# SCH_WETBCV1.net
KiCad netlist of a schematic drawn in Altium Designer
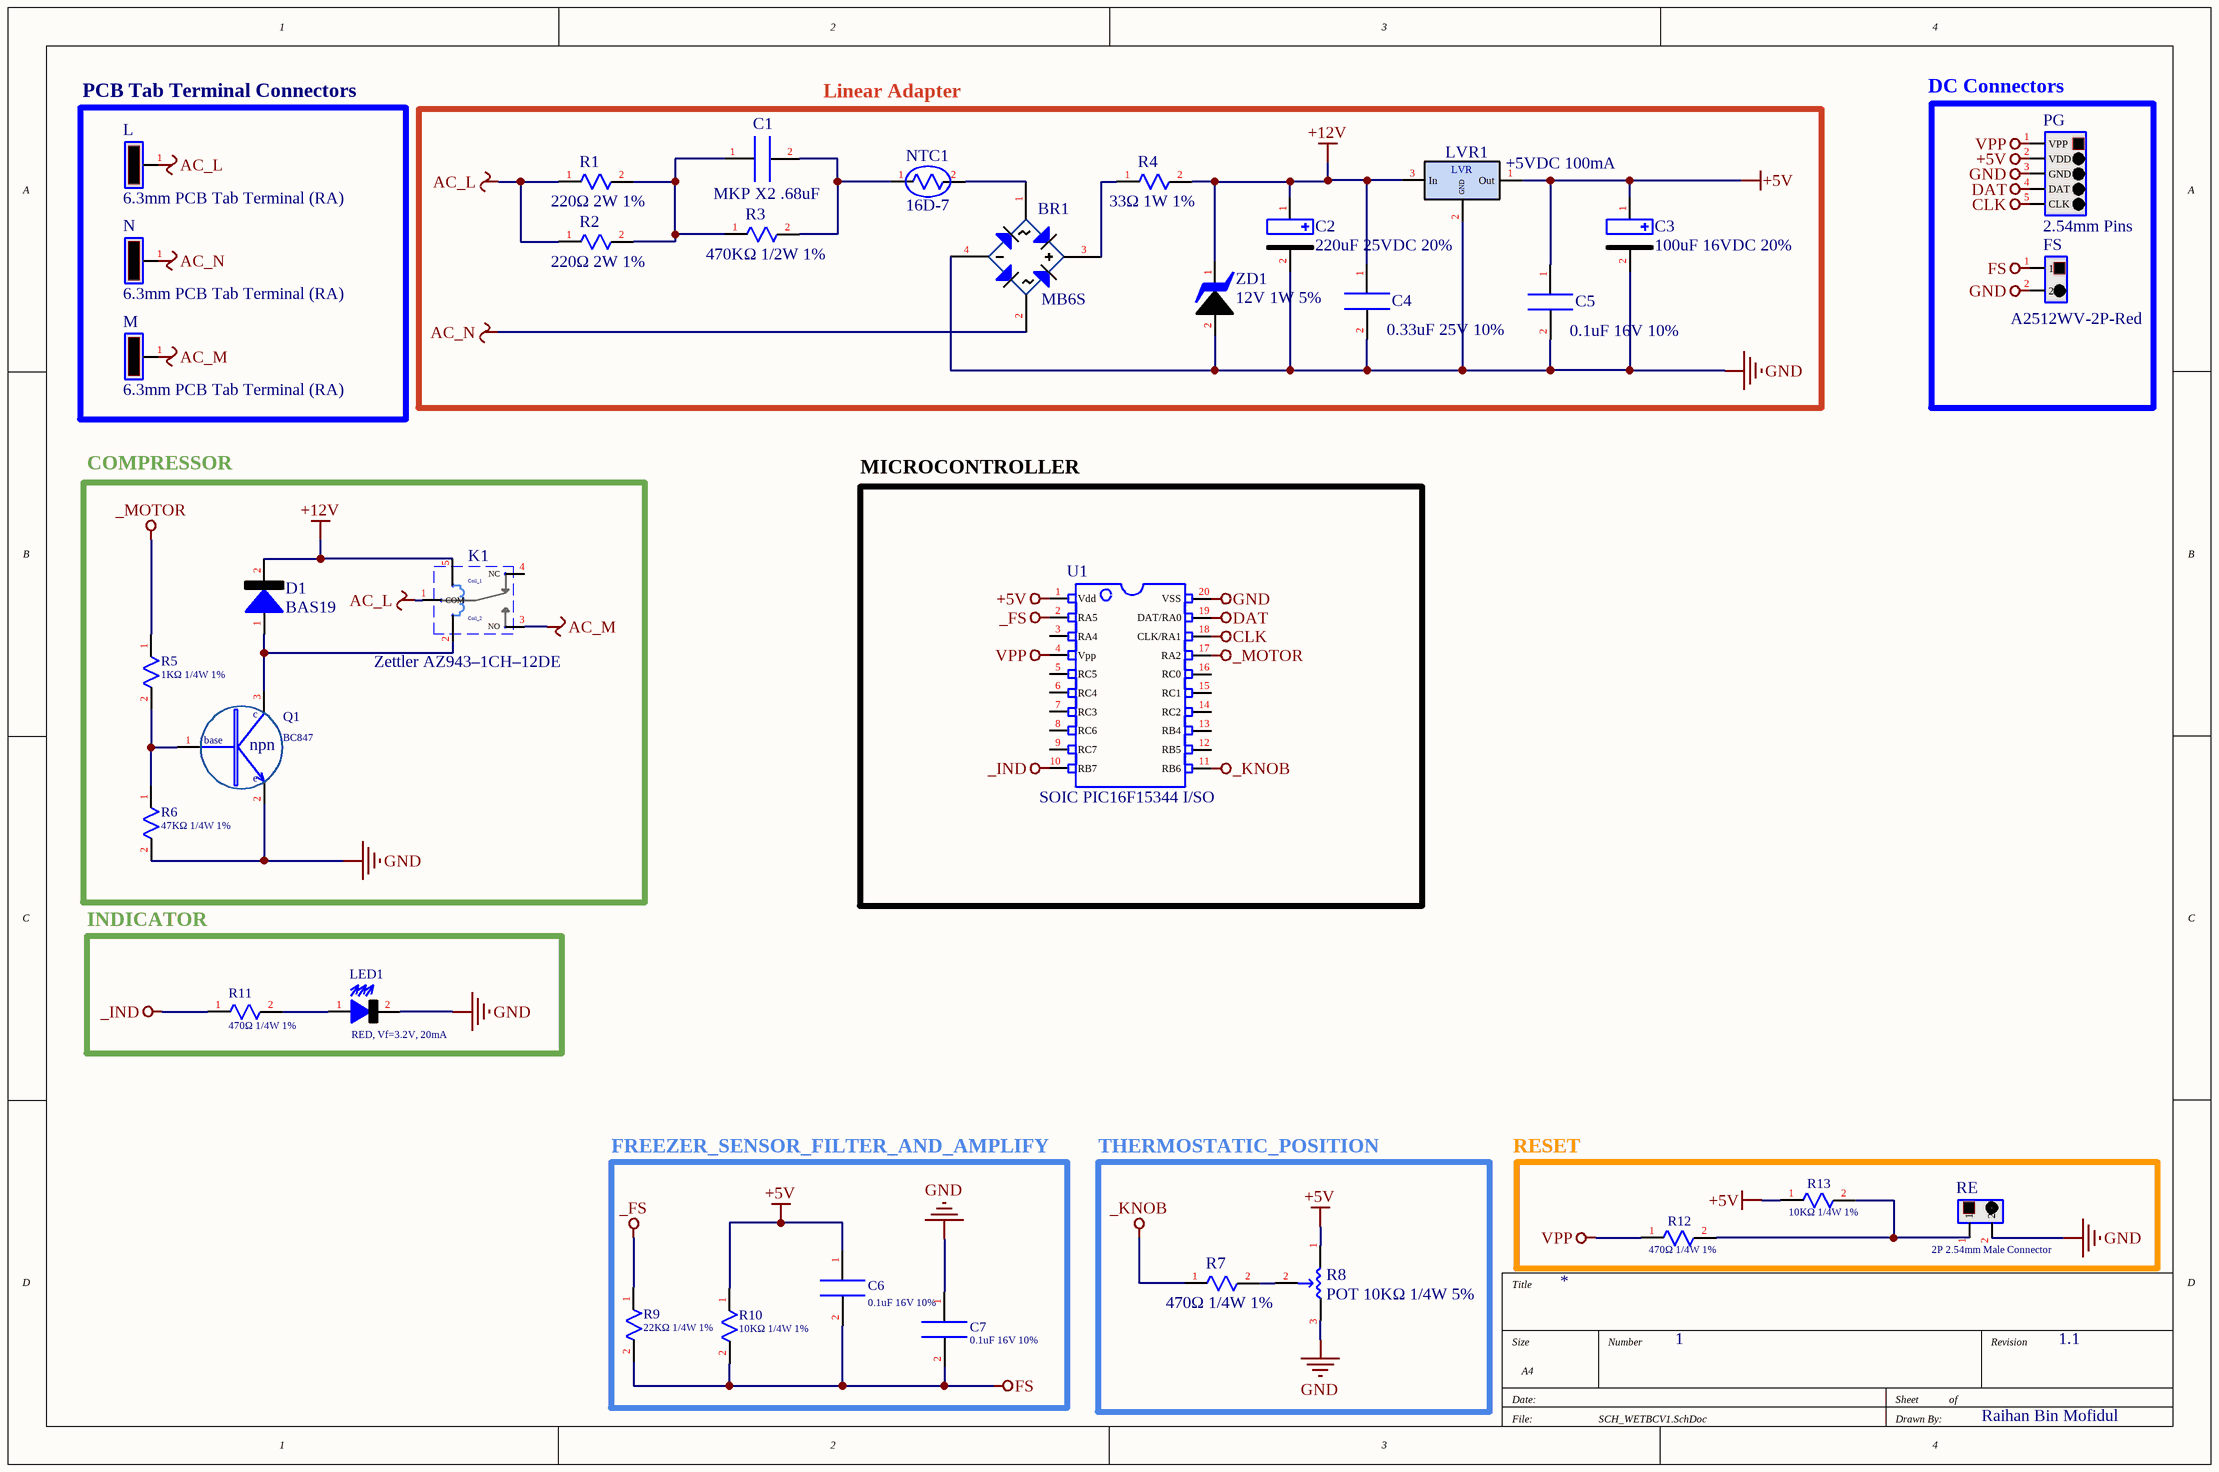
[diagram p0: SCH_WETBCV1.SchDoc]

(export (version "E")
  (design (tool "Eeschema 10.0.6"))
  (components
    (comp (ref "BR1")
      (value "MB6S")
      (footprint "BR_SMD_MB6S")
      (description "BRIDGE RECT 1P 600V 500MA 4SOIC, ON-SEMICONDUCTOR")
      (libsource (lib "RBM_SCH-LIB_02-SEP-19") (part "Bridge Rectifier"))
    )
    (comp (ref "C1")
      (value "MKP X2 .68uF")
      (footprint "C_X2_18X10X15.8_P15")
      (description "684K310V P=15 18*9.5*15.5 Climate-category: 40/110/56")
      (libsource (lib "RBM_SCH-LIB_02-SEP-19") (part "Capacitor Non-Polar"))
    )
    (comp (ref "C2")
      (value "220uF 25VDC 20%")
      (footprint "C_Radial_P3.5")
      (description "Ø8*11mm 3.5mm Pitch")
      (libsource (lib "RBM_SCH-LIB_02-SEP-19") (part "Capacitor Polar"))
    )
    (comp (ref "C3")
      (value "100uF 16VDC 20%")
      (footprint "C_Radial_P2")
      (description "Ø5*11mm 2mm Pitch")
      (libsource (lib "RBM_SCH-LIB_02-SEP-19") (part "Capacitor Polar"))
    )
    (comp (ref "C4")
      (value "0.33uF 25V 10%")
      (footprint "C_0805")
      (description "0805 Multilayer Ceramic Capacitors")
      (libsource (lib "RBM_SCH-Lib_16-Apr-19") (part "Capacitor Non-Polar"))
    )
    (comp (ref "C5")
      (value "0.1uF 16V 10%")
      (footprint "C_0805")
      (description "0805 Multilayer Ceramic Capacitors")
      (libsource (lib "RBM_SCH-Lib_16-Apr-19") (part "Capacitor Non-Polar"))
    )
    (comp (ref "C6")
      (value "0.1uF 16V 10%")
      (footprint "C_0805")
      (description "0805 Multilayer Ceramic Capacitors")
      (libsource (lib "RBM_SCH-Lib_16-Apr-19") (part "Capacitor Non-Polar"))
    )
    (comp (ref "C7")
      (value "0.1uF 16V 10%")
      (footprint "C_0805")
      (description "0805 Multilayer Ceramic Capacitors")
      (libsource (lib "RBM_SCH-Lib_16-Apr-19") (part "Capacitor Non-Polar"))
    )
    (comp (ref "D1")
      (value "BAS19")
      (footprint "D_SOT-23-3_200mA")
      (description "SOT-23-3, Diode 200mA")
      (libsource (lib "RBM_SCH-LIB_02-SEP-19") (part "Diode"))
    )
    (comp (ref "FS")
      (value "A2512WV-2P-Red")
      (footprint "CN_B2B-XH-A_WHITE")
      (libsource (lib "RBM_SCH-Lib_16-Apr-19") (part "Connector_2PINs"))
    )
    (comp (ref "K1")
      (value "Zettler AZ943–1CH–12DE")
      (footprint "K_15ARelay_AZ943-1CH-12DE")
      (libsource (lib "RBM_SCH-Lib_16-Apr-19") (part "Relay"))
    )
    (comp (ref "L")
      (value "6.3mm PCB Tab Terminal (RA)")
      (footprint "CN_6.3mm PCB Tab Terminal (Straight)")
      (libsource (lib "RBM_SCH-Lib_16-Apr-19") (part "Connector_1PIN"))
    )
    (comp (ref "LED1")
      (value "RED, Vf=3.2V, 20mA")
      (footprint "LED_3x5_P2.5")
      (description "Φ3*5mm, 2.5mm Pitch")
      (libsource (lib "RBM_SCH-LIB_02-SEP-19") (part "LED"))
    )
    (comp (ref "LVR1")
      (value "+5VDC 100mA")
      (footprint "U_CJ78L05_SOT89")
      (description "SOT-89-3L Plastic-Encapsulate Voltage Regulator")
      (libsource (lib "RBM_SCH-Lib_16-Apr-19") (part "Voltage Regulator"))
    )
    (comp (ref "M")
      (value "6.3mm PCB Tab Terminal (RA)")
      (footprint "CN_6.3mm PCB Tab Terminal (Straight)")
      (libsource (lib "RBM_SCH-Lib_16-Apr-19") (part "Connector_1PIN"))
    )
    (comp (ref "N")
      (value "6.3mm PCB Tab Terminal (RA)")
      (footprint "CN_6.3mm PCB Tab Terminal (Straight)")
      (libsource (lib "RBM_SCH-Lib_16-Apr-19") (part "Connector_1PIN"))
    )
    (comp (ref "NTC1")
      (value "16D-7")
      (footprint "NTC_5mmPitch")
      (description "5mm Pitch")
      (libsource (lib "RBM_SCH-LIB_02-SEP-19") (part "Thermistor"))
    )
    (comp (ref "PG")
      (value "2.54mm Pins")
      (footprint "CN_PIC_MCU_Debugger_Straight")
      (libsource (lib "RBM_SCH-Lib_16-Apr-19") (part "Connector_PIC_Burn"))
    )
    (comp (ref "Q1")
      (value "BC847")
      (footprint "Q_SOT-23-3_NPN_BC847")
      (description "SOT-23-3, NPN 200mA")
      (libsource (lib "RBM_SCH-Lib_16-Apr-19") (part "BJT_npn"))
    )
    (comp (ref "R1")
      (value "220Ω 2W 1%")
      (footprint "R_Axial_P15")
      (description "Metal Oxide Film Resistor, Through Hole Axial, L=12, øD=5, H=28, ød=0.6, Flame Proof")
      (libsource (lib "RBM_SCH-LIB_02-SEP-19") (part "Resistor"))
    )
    (comp (ref "R2")
      (value "220Ω 2W 1%")
      (footprint "R_Axial_P15")
      (description "Metal Oxide Film Resistor, Through Hole Axial, L=12, øD=5, H=28, ød=0.6, Flame Proof")
      (libsource (lib "RBM_SCH-LIB_02-SEP-19") (part "Resistor"))
    )
    (comp (ref "R3")
      (value "470KΩ 1/2W 1%")
      (footprint "R_Axial_P10")
      (description "Metal Oxide Film Resistor, Through Hole Axial, L=7, øD=2.5, H=28, ød=0.48, Flame Proof")
      (libsource (lib "RBM_SCH-LIB_02-SEP-19") (part "Resistor"))
    )
    (comp (ref "R4")
      (value "33Ω 1W 1%")
      (footprint "R_Axial_P15")
      (description "Metal Oxide Film Resistor, Through Hole Axial, L=10, øD=4, H=28, ød=0.5, Flame Proof")
      (libsource (lib "RBM_SCH-LIB_02-SEP-19") (part "Resistor"))
    )
    (comp (ref "R5")
      (value "1KΩ 1/4W 1%")
      (footprint "R_0805")
      (description "0805 Thick Film SMD Resistor")
      (libsource (lib "RBM_SCH-Lib_16-Apr-19") (part "Resistor"))
    )
    (comp (ref "R6")
      (value "47KΩ 1/4W 1%")
      (footprint "R_0805")
      (description "0805 Thick Film SMD Resistor")
      (libsource (lib "RBM_SCH-Lib_16-Apr-19") (part "Resistor"))
    )
    (comp (ref "R7")
      (value "470Ω 1/4W 1%")
      (footprint "R_0805")
      (description "0805 Thick Film SMD Resistor")
      (libsource (lib "RBM_SCH-LIB_02-SEP-19") (part "Resistor"))
    )
    (comp (ref "R8")
      (value "POT 10KΩ 1/4W 5%")
      (footprint "R_POT")
      (description "3Pin Potentiometer HRX09")
      (libsource (lib "RBM_SCH-LIB_02-SEP-19") (part "POT"))
    )
    (comp (ref "R9")
      (value "22KΩ 1/4W 1%")
      (footprint "R_0805")
      (description "0805 Thick Film SMD Resistor")
      (libsource (lib "RBM_SCH-Lib_16-Apr-19") (part "Resistor"))
    )
    (comp (ref "R10")
      (value "10KΩ 1/4W 1%")
      (footprint "R_0805")
      (description "0805 Thick Film SMD Resistor")
      (libsource (lib "RBM_SCH-Lib_16-Apr-19") (part "Resistor"))
    )
    (comp (ref "R11")
      (value "470Ω 1/4W 1%")
      (footprint "R_0805")
      (description "0805 Thick Film SMD Resistor")
      (libsource (lib "RBM_SCH-Lib_16-Apr-19") (part "Resistor"))
    )
    (comp (ref "R12")
      (value "470Ω 1/4W 1%")
      (footprint "R_0805")
      (description "0805 Thick Film SMD Resistor")
      (libsource (lib "RBM_SCH-Lib_16-Apr-19") (part "Resistor"))
    )
    (comp (ref "R13")
      (value "10KΩ 1/4W 1%")
      (footprint "R_0805")
      (description "0805 Thick Film SMD Resistor")
      (libsource (lib "RBM_SCH-Lib_16-Apr-19") (part "Resistor"))
    )
    (comp (ref "RE")
      (value "2P 2.54mm Male Connector")
      (footprint "CN_PIC_MCU_Reseter_Straight")
      (libsource (lib "RBM_SCH-LIB_02-SEP-19") (part "Connector_2PINs"))
    )
    (comp (ref "U1")
      (value "SOIC PIC16F15344 I/SO")
      (footprint "U_PIC16F15344_SOIC")
      (libsource (lib "RBM_SCH-Lib_16-Apr-19") (part "IC_PIC_20pins"))
    )
    (comp (ref "ZD1")
      (value "12V 1W 5%")
      (footprint "ZD_ZM4742A LL-41")
      (description "DO-213AB (glass)  (ZM4742A LL-41)")
      (libsource (lib "RBM_SCH-LIB_02-SEP-19") (part "Zener Diode"))
    )
  )
  (nets
    (net (code "1") (name "+5V") (class "Default")
      (node (ref "C3") (pin "1") (pinfunction "vdd_1") (pintype "passive"))
      (node (ref "C5") (pin "1") (pinfunction "1_1") (pintype "passive"))
      (node (ref "C6") (pin "1") (pinfunction "1_1") (pintype "passive"))
      (node (ref "LVR1") (pin "1") (pinfunction "Out_1") (pintype "passive"))
      (node (ref "PG") (pin "2") (pinfunction "VDD_2") (pintype "passive"))
      (node (ref "R10") (pin "1") (pinfunction "1_1") (pintype "passive"))
      (node (ref "R13") (pin "1") (pinfunction "1_1") (pintype "passive"))
      (node (ref "R8") (pin "1") (pinfunction "VDD_1") (pintype "passive"))
      (node (ref "U1") (pin "1") (pinfunction "Vdd_1") (pintype "passive"))
    )
    (net (code "2") (name "+12V") (class "Default")
      (node (ref "C2") (pin "1") (pinfunction "vdd_1") (pintype "passive"))
      (node (ref "C4") (pin "1") (pinfunction "1_1") (pintype "passive"))
      (node (ref "D1") (pin "2") (pinfunction "vss_2") (pintype "passive"))
      (node (ref "K1") (pin "5") (pinfunction "COIL1_5") (pintype "passive"))
      (node (ref "LVR1") (pin "3") (pinfunction "In_3") (pintype "passive"))
      (node (ref "R4") (pin "2") (pinfunction "2_2") (pintype "passive"))
      (node (ref "ZD1") (pin "1") (pinfunction "VCC_1") (pintype "passive"))
    )
    (net (code "3") (name "AC_L") (class "Default")
      (node (ref "K1") (pin "1") (pinfunction "COM_1") (pintype "passive"))
      (node (ref "L") (pin "1") (pinfunction "1_1") (pintype "passive"))
      (node (ref "R1") (pin "1") (pinfunction "1_1") (pintype "passive"))
      (node (ref "R2") (pin "1") (pinfunction "1_1") (pintype "passive"))
    )
    (net (code "4") (name "AC_M") (class "Default")
      (node (ref "K1") (pin "3") (pinfunction "NO_3") (pintype "passive"))
      (node (ref "M") (pin "1") (pinfunction "1_1") (pintype "passive"))
    )
    (net (code "5") (name "AC_N") (class "Default")
      (node (ref "BR1") (pin "2") (pinfunction "AC_2") (pintype "passive"))
      (node (ref "N") (pin "1") (pinfunction "1_1") (pintype "passive"))
    )
    (net (code "6") (name "CLK") (class "Default")
      (node (ref "PG") (pin "5") (pinfunction "CLK_5") (pintype "passive"))
      (node (ref "U1") (pin "18") (pinfunction "CLK/RA1_18") (pintype "passive"))
    )
    (net (code "7") (name "DAT") (class "Default")
      (node (ref "PG") (pin "4") (pinfunction "DAT_4") (pintype "passive"))
      (node (ref "U1") (pin "19") (pinfunction "DAT/RA0_19") (pintype "passive"))
    )
    (net (code "8") (name "FS") (class "Default")
      (node (ref "C6") (pin "2") (pinfunction "2_2") (pintype "passive"))
      (node (ref "C7") (pin "2") (pinfunction "2_2") (pintype "passive"))
      (node (ref "FS") (pin "1") (pinfunction "1_1") (pintype "passive"))
      (node (ref "R10") (pin "2") (pinfunction "2_2") (pintype "passive"))
      (node (ref "R9") (pin "2") (pinfunction "2_2") (pintype "passive"))
    )
    (net (code "9") (name "GND") (class "Default")
      (node (ref "BR1") (pin "4") (pinfunction "vss_4") (pintype "passive"))
      (node (ref "C2") (pin "2") (pinfunction "vss_2") (pintype "passive"))
      (node (ref "C3") (pin "2") (pinfunction "vss_2") (pintype "passive"))
      (node (ref "C4") (pin "2") (pinfunction "2_2") (pintype "passive"))
      (node (ref "C5") (pin "2") (pinfunction "2_2") (pintype "passive"))
      (node (ref "C7") (pin "1") (pinfunction "1_1") (pintype "passive"))
      (node (ref "FS") (pin "2") (pinfunction "2_2") (pintype "passive"))
      (node (ref "LED1") (pin "2") (pinfunction "vss_2") (pintype "passive"))
      (node (ref "LVR1") (pin "2") (pinfunction "GND_2") (pintype "passive"))
      (node (ref "PG") (pin "3") (pinfunction "GND_3") (pintype "passive"))
      (node (ref "Q1") (pin "2") (pinfunction "Emitter_2") (pintype "passive"))
      (node (ref "R6") (pin "2") (pinfunction "2_2") (pintype "passive"))
      (node (ref "R8") (pin "3") (pinfunction "VSS_3") (pintype "passive"))
      (node (ref "RE") (pin "2") (pinfunction "2_2") (pintype "passive"))
      (node (ref "U1") (pin "20") (pinfunction "VSS_20") (pintype "passive"))
      (node (ref "ZD1") (pin "2") (pinfunction "GND_2") (pintype "passive"))
    )
    (net (code "10") (name "Net-(BR1-AC-Pad1)") (class "Default")
      (node (ref "BR1") (pin "1") (pinfunction "AC_1") (pintype "passive"))
      (node (ref "NTC1") (pin "2") (pinfunction "2_2") (pintype "passive"))
    )
    (net (code "11") (name "Net-(BR1-VCC)") (class "Default")
      (node (ref "BR1") (pin "3") (pinfunction "VCC_3") (pintype "passive"))
      (node (ref "R4") (pin "1") (pinfunction "1_1") (pintype "passive"))
    )
    (net (code "12") (name "Net-(C1-Pad1)") (class "Default")
      (node (ref "C1") (pin "1") (pinfunction "1_1") (pintype "passive"))
      (node (ref "R1") (pin "2") (pinfunction "2_2") (pintype "passive"))
      (node (ref "R2") (pin "2") (pinfunction "2_2") (pintype "passive"))
      (node (ref "R3") (pin "1") (pinfunction "1_1") (pintype "passive"))
    )
    (net (code "13") (name "Net-(C1-Pad2)") (class "Default")
      (node (ref "C1") (pin "2") (pinfunction "2_2") (pintype "passive"))
      (node (ref "NTC1") (pin "1") (pinfunction "1_1") (pintype "passive"))
      (node (ref "R3") (pin "2") (pinfunction "2_2") (pintype "passive"))
    )
    (net (code "14") (name "Net-(D1-vdd)") (class "Default")
      (node (ref "D1") (pin "1") (pinfunction "vdd_1") (pintype "passive"))
      (node (ref "K1") (pin "2") (pinfunction "COIL2_2") (pintype "passive"))
      (node (ref "Q1") (pin "3") (pinfunction "Collector_3") (pintype "passive"))
    )
    (net (code "15") (name "Net-(LED1-vdd)") (class "Default")
      (node (ref "LED1") (pin "1") (pinfunction "vdd_1") (pintype "passive"))
      (node (ref "R11") (pin "2") (pinfunction "2_2") (pintype "passive"))
    )
    (net (code "16") (name "Net-(Q1-Base)") (class "Default")
      (node (ref "Q1") (pin "1") (pinfunction "Base_1") (pintype "passive"))
      (node (ref "R5") (pin "2") (pinfunction "2_2") (pintype "passive"))
      (node (ref "R6") (pin "1") (pinfunction "1_1") (pintype "passive"))
    )
    (net (code "17") (name "Net-(R8-POT)") (class "Default")
      (node (ref "R7") (pin "2") (pinfunction "2_2") (pintype "passive"))
      (node (ref "R8") (pin "2") (pinfunction "POT_2") (pintype "passive"))
    )
    (net (code "18") (name "Net-(R12-Pad2)") (class "Default")
      (node (ref "R12") (pin "2") (pinfunction "2_2") (pintype "passive"))
      (node (ref "R13") (pin "2") (pinfunction "2_2") (pintype "passive"))
      (node (ref "RE") (pin "1") (pinfunction "1_1") (pintype "passive"))
    )
    (net (code "19") (name "VPP") (class "Default")
      (node (ref "PG") (pin "1") (pinfunction "VPP_1") (pintype "passive"))
      (node (ref "R12") (pin "1") (pinfunction "1_1") (pintype "passive"))
      (node (ref "U1") (pin "4") (pinfunction "Vpp_4") (pintype "passive"))
    )
    (net (code "20") (name "_FS") (class "Default")
      (node (ref "R9") (pin "1") (pinfunction "1_1") (pintype "passive"))
      (node (ref "U1") (pin "2") (pinfunction "RA5_2") (pintype "passive"))
    )
    (net (code "21") (name "_IND") (class "Default")
      (node (ref "R11") (pin "1") (pinfunction "1_1") (pintype "passive"))
      (node (ref "U1") (pin "10") (pinfunction "RB7_10") (pintype "passive"))
    )
    (net (code "22") (name "_KNOB") (class "Default")
      (node (ref "R7") (pin "1") (pinfunction "1_1") (pintype "passive"))
      (node (ref "U1") (pin "11") (pinfunction "RB6_11") (pintype "passive"))
    )
    (net (code "23") (name "_MOTOR") (class "Default")
      (node (ref "R5") (pin "1") (pinfunction "1_1") (pintype "passive"))
      (node (ref "U1") (pin "17") (pinfunction "RA2_17") (pintype "passive"))
    )
    (net (code "24") (name "unconnected-(K1-NC-Pad4)") (class "Default")
      (node (ref "K1") (pin "4") (pinfunction "NC_4") (pintype "passive"))
    )
    (net (code "25") (name "unconnected-(U1-RA4-Pad3)") (class "Default")
      (node (ref "U1") (pin "3") (pinfunction "RA4_3") (pintype "passive"))
    )
    (net (code "26") (name "unconnected-(U1-RB4-Pad13)") (class "Default")
      (node (ref "U1") (pin "13") (pinfunction "RB4_13") (pintype "passive"))
    )
    (net (code "27") (name "unconnected-(U1-RB5-Pad12)") (class "Default")
      (node (ref "U1") (pin "12") (pinfunction "RB5_12") (pintype "passive"))
    )
    (net (code "28") (name "unconnected-(U1-RC0-Pad16)") (class "Default")
      (node (ref "U1") (pin "16") (pinfunction "RC0_16") (pintype "passive"))
    )
    (net (code "29") (name "unconnected-(U1-RC1-Pad15)") (class "Default")
      (node (ref "U1") (pin "15") (pinfunction "RC1_15") (pintype "passive"))
    )
    (net (code "30") (name "unconnected-(U1-RC2-Pad14)") (class "Default")
      (node (ref "U1") (pin "14") (pinfunction "RC2_14") (pintype "passive"))
    )
    (net (code "31") (name "unconnected-(U1-RC3-Pad7)") (class "Default")
      (node (ref "U1") (pin "7") (pinfunction "RC3_7") (pintype "passive"))
    )
    (net (code "32") (name "unconnected-(U1-RC4-Pad6)") (class "Default")
      (node (ref "U1") (pin "6") (pinfunction "RC4_6") (pintype "passive"))
    )
    (net (code "33") (name "unconnected-(U1-RC5-Pad5)") (class "Default")
      (node (ref "U1") (pin "5") (pinfunction "RC5_5") (pintype "passive"))
    )
    (net (code "34") (name "unconnected-(U1-RC6-Pad8)") (class "Default")
      (node (ref "U1") (pin "8") (pinfunction "RC6_8") (pintype "passive"))
    )
    (net (code "35") (name "unconnected-(U1-RC7-Pad9)") (class "Default")
      (node (ref "U1") (pin "9") (pinfunction "RC7_9") (pintype "passive"))
    )
  )
)
